# SDRAM.net
KiCad netlist of a schematic drawn in Altium Designer
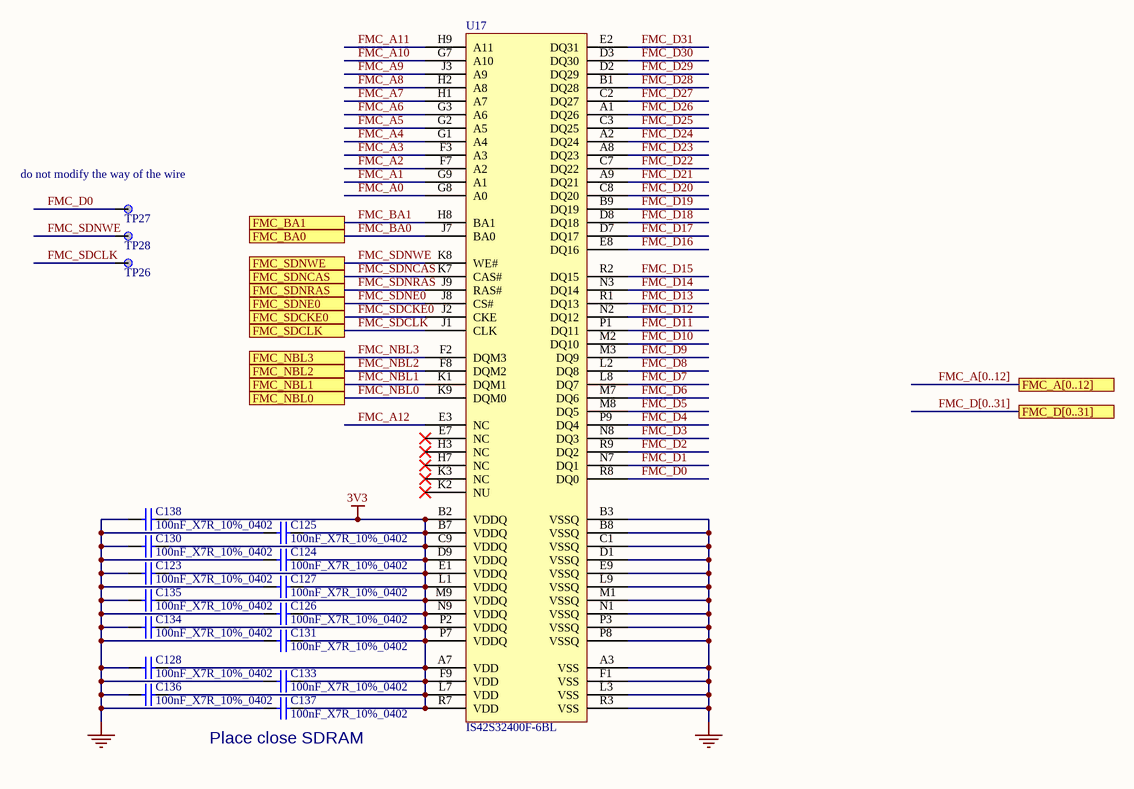
[diagram p0: SDRAM.SchDoc]

(export (version "E")
  (design (tool "Eeschema 10.0.6"))
  (components
    (comp (ref "C123")
      (value "100nF_X7R_10%_0402")
      (footprint "0402C")
      (description "Capacitor,100nF,16V,X7R,10%,0402,YAGEO")
      (libsource (lib "MCD_TOOLS") (part "Cap_100nF_X7R_10%_0402"))
    )
    (comp (ref "C124")
      (value "100nF_X7R_10%_0402")
      (footprint "0402C")
      (description "Capacitor,100nF,16V,X7R,10%,0402,YAGEO")
      (libsource (lib "MCD_TOOLS") (part "Cap_100nF_X7R_10%_0402"))
    )
    (comp (ref "C125")
      (value "100nF_X7R_10%_0402")
      (footprint "0402C")
      (description "Capacitor,100nF,16V,X7R,10%,0402,YAGEO")
      (libsource (lib "MCD_TOOLS") (part "Cap_100nF_X7R_10%_0402"))
    )
    (comp (ref "C126")
      (value "100nF_X7R_10%_0402")
      (footprint "0402C")
      (description "Capacitor,100nF,16V,X7R,10%,0402,YAGEO")
      (libsource (lib "MCD_TOOLS") (part "Cap_100nF_X7R_10%_0402"))
    )
    (comp (ref "C127")
      (value "100nF_X7R_10%_0402")
      (footprint "0402C")
      (description "Capacitor,100nF,16V,X7R,10%,0402,YAGEO")
      (libsource (lib "MCD_TOOLS") (part "Cap_100nF_X7R_10%_0402"))
    )
    (comp (ref "C128")
      (value "100nF_X7R_10%_0402")
      (footprint "0402C")
      (description "Capacitor,100nF,16V,X7R,10%,0402,YAGEO")
      (libsource (lib "MCD_TOOLS") (part "Cap_100nF_X7R_10%_0402"))
    )
    (comp (ref "C130")
      (value "100nF_X7R_10%_0402")
      (footprint "0402C")
      (description "Capacitor,100nF,16V,X7R,10%,0402,YAGEO")
      (libsource (lib "MCD_TOOLS") (part "Cap_100nF_X7R_10%_0402"))
    )
    (comp (ref "C131")
      (value "100nF_X7R_10%_0402")
      (footprint "0402C")
      (description "Capacitor,100nF,16V,X7R,10%,0402,YAGEO")
      (libsource (lib "MCD_TOOLS") (part "Cap_100nF_X7R_10%_0402"))
    )
    (comp (ref "C133")
      (value "100nF_X7R_10%_0402")
      (footprint "0402C")
      (description "Capacitor,100nF,16V,X7R,10%,0402,YAGEO")
      (libsource (lib "MCD_TOOLS") (part "Cap_100nF_X7R_10%_0402"))
    )
    (comp (ref "C134")
      (value "100nF_X7R_10%_0402")
      (footprint "0402C")
      (description "Capacitor,100nF,16V,X7R,10%,0402,YAGEO")
      (libsource (lib "MCD_TOOLS") (part "Cap_100nF_X7R_10%_0402"))
    )
    (comp (ref "C135")
      (value "100nF_X7R_10%_0402")
      (footprint "0402C")
      (description "Capacitor,100nF,16V,X7R,10%,0402,YAGEO")
      (libsource (lib "MCD_TOOLS") (part "Cap_100nF_X7R_10%_0402"))
    )
    (comp (ref "C136")
      (value "100nF_X7R_10%_0402")
      (footprint "0402C")
      (description "Capacitor,100nF,16V,X7R,10%,0402,YAGEO")
      (libsource (lib "MCD_TOOLS") (part "Cap_100nF_X7R_10%_0402"))
    )
    (comp (ref "C137")
      (value "100nF_X7R_10%_0402")
      (footprint "0402C")
      (description "Capacitor,100nF,16V,X7R,10%,0402,YAGEO")
      (libsource (lib "MCD_TOOLS") (part "Cap_100nF_X7R_10%_0402"))
    )
    (comp (ref "C138")
      (value "100nF_X7R_10%_0402")
      (footprint "0402C")
      (description "Capacitor,100nF,16V,X7R,10%,0402,YAGEO")
      (libsource (lib "MCD_TOOLS") (part "Cap_100nF_X7R_10%_0402"))
    )
    (comp (ref "TP26")
      (value "TP")
      (footprint "TP_C40")
      (description "Test Point")
      (libsource (lib "MCD_TOOLS_CONNECTOR") (part "TP"))
    )
    (comp (ref "TP27")
      (value "TP")
      (footprint "TP_C40")
      (description "Test Point")
      (libsource (lib "MCD_TOOLS_CONNECTOR") (part "TP"))
    )
    (comp (ref "TP28")
      (value "TP")
      (footprint "TP_C40")
      (description "Test Point")
      (libsource (lib "MCD_TOOLS_CONNECTOR") (part "TP"))
    )
    (comp (ref "U17")
      (value "IS42S32400F-6BL")
      (footprint "ICC_VFBGA90_8X13_P080")
      (description "SDRAM 128MBit 166MHZ 90BGA")
      (fields
        (field (name "INTERNAL_PART_NUMBER") "MCD-01977")
        (field (name "MANUFACTURER") "ISSI")
        (field (name "PROVIDED_BY") "SUBCO")
      )
      (libsource (lib "MCD_PARTS_database") (part "IS42S32400F-6BL"))
    )
  )
  (nets
    (net (code "1") (name "/FMC_A0") (class "Default")
      (node (ref "U17") (pin "G8") (pinfunction "A0_G8") (pintype "passive"))
    )
    (net (code "2") (name "/FMC_A1") (class "Default")
      (node (ref "U17") (pin "G9") (pinfunction "A1_G9") (pintype "passive"))
    )
    (net (code "3") (name "/FMC_A2") (class "Default")
      (node (ref "U17") (pin "F7") (pinfunction "A2_F7") (pintype "passive"))
    )
    (net (code "4") (name "/FMC_A3") (class "Default")
      (node (ref "U17") (pin "F3") (pinfunction "A3_F3") (pintype "passive"))
    )
    (net (code "5") (name "/FMC_A4") (class "Default")
      (node (ref "U17") (pin "G1") (pinfunction "A4_G1") (pintype "passive"))
    )
    (net (code "6") (name "/FMC_A5") (class "Default")
      (node (ref "U17") (pin "G2") (pinfunction "A5_G2") (pintype "passive"))
    )
    (net (code "7") (name "/FMC_A6") (class "Default")
      (node (ref "U17") (pin "G3") (pinfunction "A6_G3") (pintype "passive"))
    )
    (net (code "8") (name "/FMC_A7") (class "Default")
      (node (ref "U17") (pin "H1") (pinfunction "A7_H1") (pintype "passive"))
    )
    (net (code "9") (name "/FMC_A8") (class "Default")
      (node (ref "U17") (pin "H2") (pinfunction "A8_H2") (pintype "passive"))
    )
    (net (code "10") (name "/FMC_A9") (class "Default")
      (node (ref "U17") (pin "J3") (pinfunction "A9_J3") (pintype "passive"))
    )
    (net (code "11") (name "/FMC_A10") (class "Default")
      (node (ref "U17") (pin "G7") (pinfunction "A10_G7") (pintype "passive"))
    )
    (net (code "12") (name "/FMC_A11") (class "Default")
      (node (ref "U17") (pin "H9") (pinfunction "A11_H9") (pintype "passive"))
    )
    (net (code "13") (name "/FMC_A12") (class "Default")
      (node (ref "U17") (pin "E3") (pinfunction "NC_E3") (pintype "passive"))
    )
    (net (code "15") (name "/FMC_BA0") (class "Default")
      (node (ref "U17") (pin "J7") (pinfunction "BA0_J7") (pintype "passive"))
    )
    (net (code "16") (name "/FMC_BA1") (class "Default")
      (node (ref "U17") (pin "H8") (pinfunction "BA1_H8") (pintype "passive"))
    )
    (net (code "17") (name "/FMC_D0") (class "Default")
      (node (ref "TP27") (pin "1") (pinfunction "1_1") (pintype "passive"))
      (node (ref "U17") (pin "R8") (pinfunction "DQ0_R8") (pintype "passive"))
    )
    (net (code "18") (name "/FMC_D1") (class "Default")
      (node (ref "U17") (pin "N7") (pinfunction "DQ1_N7") (pintype "passive"))
    )
    (net (code "19") (name "/FMC_D2") (class "Default")
      (node (ref "U17") (pin "R9") (pinfunction "DQ2_R9") (pintype "passive"))
    )
    (net (code "20") (name "/FMC_D3") (class "Default")
      (node (ref "U17") (pin "N8") (pinfunction "DQ3_N8") (pintype "passive"))
    )
    (net (code "21") (name "/FMC_D4") (class "Default")
      (node (ref "U17") (pin "P9") (pinfunction "DQ4_P9") (pintype "passive"))
    )
    (net (code "22") (name "/FMC_D5") (class "Default")
      (node (ref "U17") (pin "M8") (pinfunction "DQ5_M8") (pintype "passive"))
    )
    (net (code "23") (name "/FMC_D6") (class "Default")
      (node (ref "U17") (pin "M7") (pinfunction "DQ6_M7") (pintype "passive"))
    )
    (net (code "24") (name "/FMC_D7") (class "Default")
      (node (ref "U17") (pin "L8") (pinfunction "DQ7_L8") (pintype "passive"))
    )
    (net (code "25") (name "/FMC_D8") (class "Default")
      (node (ref "U17") (pin "L2") (pinfunction "DQ8_L2") (pintype "passive"))
    )
    (net (code "26") (name "/FMC_D9") (class "Default")
      (node (ref "U17") (pin "M3") (pinfunction "DQ9_M3") (pintype "passive"))
    )
    (net (code "27") (name "/FMC_D10") (class "Default")
      (node (ref "U17") (pin "M2") (pinfunction "DQ10_M2") (pintype "passive"))
    )
    (net (code "28") (name "/FMC_D11") (class "Default")
      (node (ref "U17") (pin "P1") (pinfunction "DQ11_P1") (pintype "passive"))
    )
    (net (code "29") (name "/FMC_D12") (class "Default")
      (node (ref "U17") (pin "N2") (pinfunction "DQ12_N2") (pintype "passive"))
    )
    (net (code "30") (name "/FMC_D13") (class "Default")
      (node (ref "U17") (pin "R1") (pinfunction "DQ13_R1") (pintype "passive"))
    )
    (net (code "31") (name "/FMC_D14") (class "Default")
      (node (ref "U17") (pin "N3") (pinfunction "DQ14_N3") (pintype "passive"))
    )
    (net (code "32") (name "/FMC_D15") (class "Default")
      (node (ref "U17") (pin "R2") (pinfunction "DQ15_R2") (pintype "passive"))
    )
    (net (code "33") (name "/FMC_D16") (class "Default")
      (node (ref "U17") (pin "E8") (pinfunction "DQ16_E8") (pintype "passive"))
    )
    (net (code "34") (name "/FMC_D17") (class "Default")
      (node (ref "U17") (pin "D7") (pinfunction "DQ17_D7") (pintype "passive"))
    )
    (net (code "35") (name "/FMC_D18") (class "Default")
      (node (ref "U17") (pin "D8") (pinfunction "DQ18_D8") (pintype "passive"))
    )
    (net (code "36") (name "/FMC_D19") (class "Default")
      (node (ref "U17") (pin "B9") (pinfunction "DQ19_B9") (pintype "passive"))
    )
    (net (code "37") (name "/FMC_D20") (class "Default")
      (node (ref "U17") (pin "C8") (pinfunction "DQ20_C8") (pintype "passive"))
    )
    (net (code "38") (name "/FMC_D21") (class "Default")
      (node (ref "U17") (pin "A9") (pinfunction "DQ21_A9") (pintype "passive"))
    )
    (net (code "39") (name "/FMC_D22") (class "Default")
      (node (ref "U17") (pin "C7") (pinfunction "DQ22_C7") (pintype "passive"))
    )
    (net (code "40") (name "/FMC_D23") (class "Default")
      (node (ref "U17") (pin "A8") (pinfunction "DQ23_A8") (pintype "passive"))
    )
    (net (code "41") (name "/FMC_D24") (class "Default")
      (node (ref "U17") (pin "A2") (pinfunction "DQ24_A2") (pintype "passive"))
    )
    (net (code "42") (name "/FMC_D25") (class "Default")
      (node (ref "U17") (pin "C3") (pinfunction "DQ25_C3") (pintype "passive"))
    )
    (net (code "43") (name "/FMC_D26") (class "Default")
      (node (ref "U17") (pin "A1") (pinfunction "DQ26_A1") (pintype "passive"))
    )
    (net (code "44") (name "/FMC_D27") (class "Default")
      (node (ref "U17") (pin "C2") (pinfunction "DQ27_C2") (pintype "passive"))
    )
    (net (code "45") (name "/FMC_D28") (class "Default")
      (node (ref "U17") (pin "B1") (pinfunction "DQ28_B1") (pintype "passive"))
    )
    (net (code "46") (name "/FMC_D29") (class "Default")
      (node (ref "U17") (pin "D2") (pinfunction "DQ29_D2") (pintype "passive"))
    )
    (net (code "47") (name "/FMC_D30") (class "Default")
      (node (ref "U17") (pin "D3") (pinfunction "DQ30_D3") (pintype "passive"))
    )
    (net (code "48") (name "/FMC_D31") (class "Default")
      (node (ref "U17") (pin "E2") (pinfunction "DQ31_E2") (pintype "passive"))
    )
    (net (code "50") (name "/FMC_NBL0") (class "Default")
      (node (ref "U17") (pin "K9") (pinfunction "DQM0_K9") (pintype "passive"))
    )
    (net (code "51") (name "/FMC_NBL1") (class "Default")
      (node (ref "U17") (pin "K1") (pinfunction "DQM1_K1") (pintype "passive"))
    )
    (net (code "52") (name "/FMC_NBL2") (class "Default")
      (node (ref "U17") (pin "F8") (pinfunction "DQM2_F8") (pintype "passive"))
    )
    (net (code "53") (name "/FMC_NBL3") (class "Default")
      (node (ref "U17") (pin "F2") (pinfunction "DQM3_F2") (pintype "passive"))
    )
    (net (code "54") (name "/FMC_SDCKE0") (class "Default")
      (node (ref "U17") (pin "J2") (pinfunction "CKE_J2") (pintype "passive"))
    )
    (net (code "55") (name "/FMC_SDCLK") (class "Default")
      (node (ref "TP26") (pin "1") (pinfunction "1_1") (pintype "passive"))
      (node (ref "U17") (pin "J1") (pinfunction "CLK_J1") (pintype "passive"))
    )
    (net (code "56") (name "/FMC_SDNCAS") (class "Default")
      (node (ref "U17") (pin "K7") (pinfunction "CAS#_K7") (pintype "passive"))
    )
    (net (code "57") (name "/FMC_SDNE0") (class "Default")
      (node (ref "U17") (pin "J8") (pinfunction "CS#_J8") (pintype "passive"))
    )
    (net (code "58") (name "/FMC_SDNRAS") (class "Default")
      (node (ref "U17") (pin "J9") (pinfunction "RAS#_J9") (pintype "passive"))
    )
    (net (code "59") (name "/FMC_SDNWE") (class "Default")
      (node (ref "TP28") (pin "1") (pinfunction "1_1") (pintype "passive"))
      (node (ref "U17") (pin "K8") (pinfunction "WE#_K8") (pintype "passive"))
    )
    (net (code "60") (name "3V3") (class "Default")
      (node (ref "C123") (pin "2") (pinfunction "2_2") (pintype "passive"))
      (node (ref "C124") (pin "2") (pinfunction "2_2") (pintype "passive"))
      (node (ref "C125") (pin "2") (pinfunction "2_2") (pintype "passive"))
      (node (ref "C126") (pin "2") (pinfunction "2_2") (pintype "passive"))
      (node (ref "C127") (pin "2") (pinfunction "2_2") (pintype "passive"))
      (node (ref "C128") (pin "2") (pinfunction "2_2") (pintype "passive"))
      (node (ref "C130") (pin "2") (pinfunction "2_2") (pintype "passive"))
      (node (ref "C131") (pin "2") (pinfunction "2_2") (pintype "passive"))
      (node (ref "C133") (pin "2") (pinfunction "2_2") (pintype "passive"))
      (node (ref "C134") (pin "2") (pinfunction "2_2") (pintype "passive"))
      (node (ref "C135") (pin "2") (pinfunction "2_2") (pintype "passive"))
      (node (ref "C136") (pin "2") (pinfunction "2_2") (pintype "passive"))
      (node (ref "C137") (pin "2") (pinfunction "2_2") (pintype "passive"))
      (node (ref "C138") (pin "2") (pinfunction "2_2") (pintype "passive"))
      (node (ref "U17") (pin "A7") (pinfunction "VDD_A7") (pintype "passive"))
      (node (ref "U17") (pin "B2") (pinfunction "VDDQ_B2") (pintype "passive"))
      (node (ref "U17") (pin "B7") (pinfunction "VDDQ_B7") (pintype "passive"))
      (node (ref "U17") (pin "C9") (pinfunction "VDDQ_C9") (pintype "passive"))
      (node (ref "U17") (pin "D9") (pinfunction "VDDQ_D9") (pintype "passive"))
      (node (ref "U17") (pin "E1") (pinfunction "VDDQ_E1") (pintype "passive"))
      (node (ref "U17") (pin "F9") (pinfunction "VDD_F9") (pintype "passive"))
      (node (ref "U17") (pin "L1") (pinfunction "VDDQ_L1") (pintype "passive"))
      (node (ref "U17") (pin "L7") (pinfunction "VDD_L7") (pintype "passive"))
      (node (ref "U17") (pin "M9") (pinfunction "VDDQ_M9") (pintype "passive"))
      (node (ref "U17") (pin "N9") (pinfunction "VDDQ_N9") (pintype "passive"))
      (node (ref "U17") (pin "P2") (pinfunction "VDDQ_P2") (pintype "passive"))
      (node (ref "U17") (pin "P7") (pinfunction "VDDQ_P7") (pintype "passive"))
      (node (ref "U17") (pin "R7") (pinfunction "VDD_R7") (pintype "passive"))
    )
    (net (code "61") (name "GND") (class "Default")
      (node (ref "C123") (pin "1") (pinfunction "1_1") (pintype "passive"))
      (node (ref "C124") (pin "1") (pinfunction "1_1") (pintype "passive"))
      (node (ref "C125") (pin "1") (pinfunction "1_1") (pintype "passive"))
      (node (ref "C126") (pin "1") (pinfunction "1_1") (pintype "passive"))
      (node (ref "C127") (pin "1") (pinfunction "1_1") (pintype "passive"))
      (node (ref "C128") (pin "1") (pinfunction "1_1") (pintype "passive"))
      (node (ref "C130") (pin "1") (pinfunction "1_1") (pintype "passive"))
      (node (ref "C131") (pin "1") (pinfunction "1_1") (pintype "passive"))
      (node (ref "C133") (pin "1") (pinfunction "1_1") (pintype "passive"))
      (node (ref "C134") (pin "1") (pinfunction "1_1") (pintype "passive"))
      (node (ref "C135") (pin "1") (pinfunction "1_1") (pintype "passive"))
      (node (ref "C136") (pin "1") (pinfunction "1_1") (pintype "passive"))
      (node (ref "C137") (pin "1") (pinfunction "1_1") (pintype "passive"))
      (node (ref "C138") (pin "1") (pinfunction "1_1") (pintype "passive"))
      (node (ref "U17") (pin "A3") (pinfunction "VSS_A3") (pintype "passive"))
      (node (ref "U17") (pin "B3") (pinfunction "VSSQ_B3") (pintype "passive"))
      (node (ref "U17") (pin "B8") (pinfunction "VSSQ_B8") (pintype "passive"))
      (node (ref "U17") (pin "C1") (pinfunction "VSSQ_C1") (pintype "passive"))
      (node (ref "U17") (pin "D1") (pinfunction "VSSQ_D1") (pintype "passive"))
      (node (ref "U17") (pin "E9") (pinfunction "VSSQ_E9") (pintype "passive"))
      (node (ref "U17") (pin "F1") (pinfunction "VSS_F1") (pintype "passive"))
      (node (ref "U17") (pin "L3") (pinfunction "VSS_L3") (pintype "passive"))
      (node (ref "U17") (pin "L9") (pinfunction "VSSQ_L9") (pintype "passive"))
      (node (ref "U17") (pin "M1") (pinfunction "VSSQ_M1") (pintype "passive"))
      (node (ref "U17") (pin "N1") (pinfunction "VSSQ_N1") (pintype "passive"))
      (node (ref "U17") (pin "P3") (pinfunction "VSSQ_P3") (pintype "passive"))
      (node (ref "U17") (pin "P8") (pinfunction "VSSQ_P8") (pintype "passive"))
      (node (ref "U17") (pin "R3") (pinfunction "VSS_R3") (pintype "passive"))
    )
    (net (code "62") (name "unconnected-(U17-NC-PadE7)") (class "Default")
      (node (ref "U17") (pin "E7") (pinfunction "NC_E7") (pintype "passive+no_connect"))
    )
    (net (code "63") (name "unconnected-(U17-NC-PadH3)") (class "Default")
      (node (ref "U17") (pin "H3") (pinfunction "NC_H3") (pintype "passive+no_connect"))
    )
    (net (code "64") (name "unconnected-(U17-NC-PadH7)") (class "Default")
      (node (ref "U17") (pin "H7") (pinfunction "NC_H7") (pintype "passive+no_connect"))
    )
    (net (code "65") (name "unconnected-(U17-NC-PadK3)") (class "Default")
      (node (ref "U17") (pin "K3") (pinfunction "NC_K3") (pintype "passive+no_connect"))
    )
    (net (code "66") (name "unconnected-(U17-NU-PadK2)") (class "Default")
      (node (ref "U17") (pin "K2") (pinfunction "NU_K2") (pintype "passive+no_connect"))
    )
  )
)
